# Qwiic_Mux.net
KiCad netlist of a schematic drawn in EAGLE
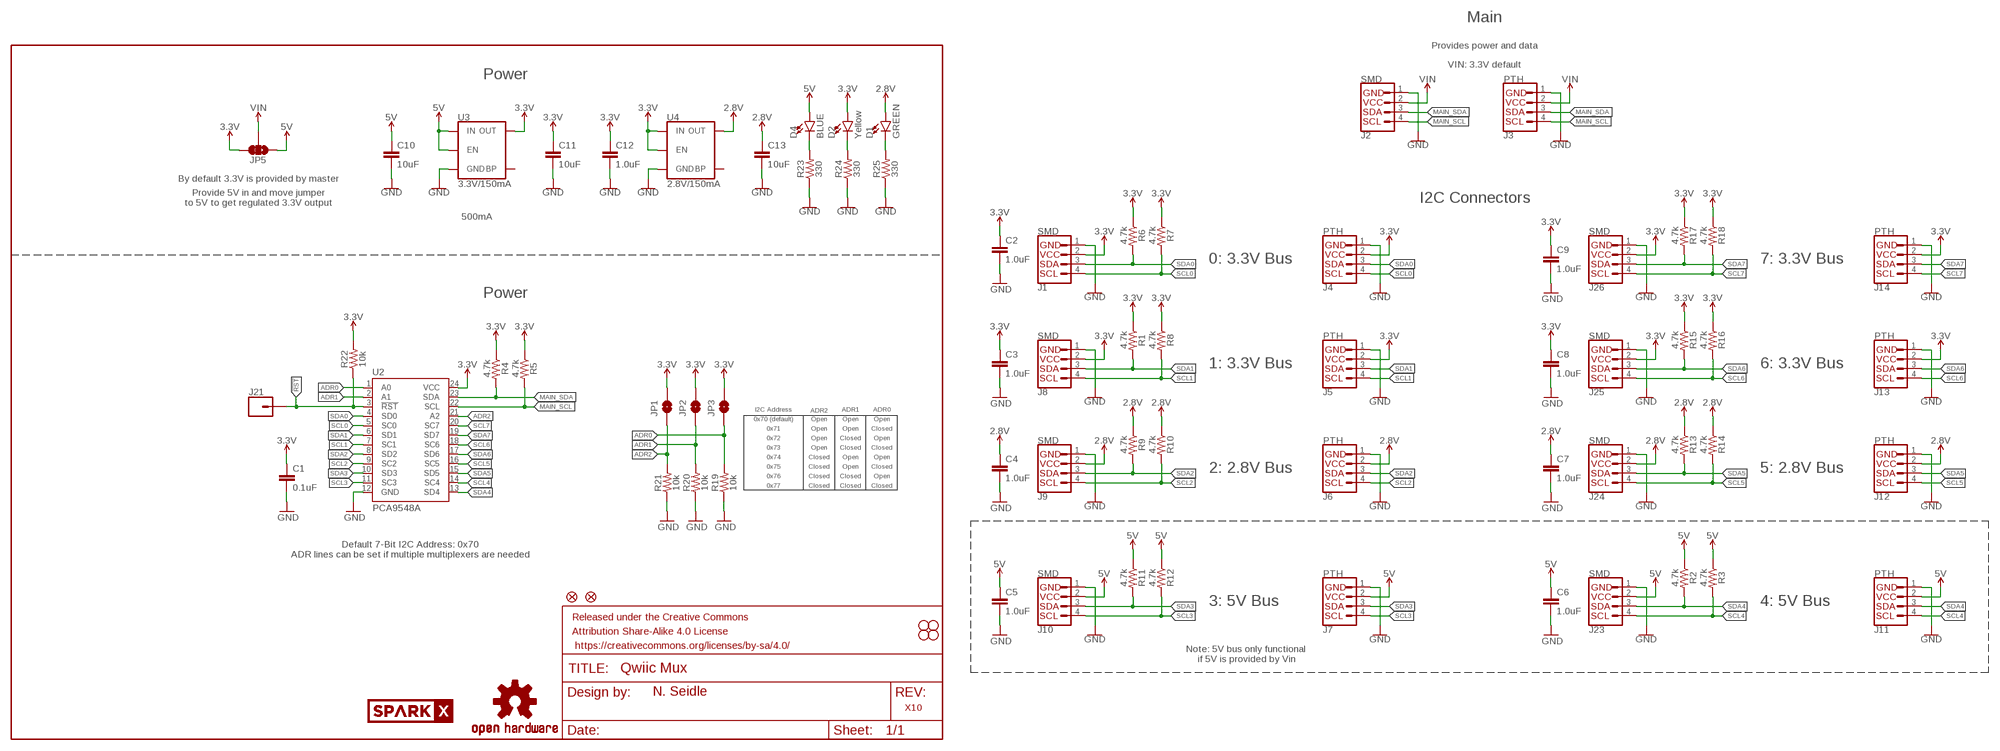
[diagram p0: schematic, sheet 1]

(export (version "E")
  (design (tool "Eeschema 10.0.6"))
  (components
    (comp (ref "C1")
      (value "0.1uF")
      (footprint "eagle-import:0603")
      (libsource (lib "eagle-import") (part "0.1UF-0603-25V-(+80/-20%)"))
    )
    (comp (ref "C2")
      (value "1.0uF")
      (footprint "eagle-import:0603")
      (libsource (lib "eagle-import") (part "1.0UF-0603-16V-10%"))
    )
    (comp (ref "C3")
      (value "1.0uF")
      (footprint "eagle-import:0603")
      (libsource (lib "eagle-import") (part "1.0UF-0603-16V-10%"))
    )
    (comp (ref "C4")
      (value "1.0uF")
      (footprint "eagle-import:0603")
      (libsource (lib "eagle-import") (part "1.0UF-0603-16V-10%"))
    )
    (comp (ref "C5")
      (value "1.0uF")
      (footprint "eagle-import:0603")
      (libsource (lib "eagle-import") (part "1.0UF-0603-16V-10%"))
    )
    (comp (ref "C6")
      (value "1.0uF")
      (footprint "eagle-import:0603")
      (libsource (lib "eagle-import") (part "1.0UF-0603-16V-10%"))
    )
    (comp (ref "C7")
      (value "1.0uF")
      (footprint "eagle-import:0603")
      (libsource (lib "eagle-import") (part "1.0UF-0603-16V-10%"))
    )
    (comp (ref "C8")
      (value "1.0uF")
      (footprint "eagle-import:0603")
      (libsource (lib "eagle-import") (part "1.0UF-0603-16V-10%"))
    )
    (comp (ref "C9")
      (value "1.0uF")
      (footprint "eagle-import:0603")
      (libsource (lib "eagle-import") (part "1.0UF-0603-16V-10%"))
    )
    (comp (ref "C10")
      (value "10uF")
      (footprint "eagle-import:0603")
      (libsource (lib "eagle-import") (part "10UF-0603-6.3V-20%"))
    )
    (comp (ref "C11")
      (value "10uF")
      (footprint "eagle-import:0603")
      (libsource (lib "eagle-import") (part "10UF-0603-6.3V-20%"))
    )
    (comp (ref "C12")
      (value "1.0uF")
      (footprint "eagle-import:0603")
      (libsource (lib "eagle-import") (part "1.0UF-0603-16V-10%"))
    )
    (comp (ref "C13")
      (value "10uF")
      (footprint "eagle-import:0603")
      (libsource (lib "eagle-import") (part "10UF-0603-6.3V-20%"))
    )
    (comp (ref "D1")
      (value "GREEN")
      (footprint "eagle-import:LED-0603")
      (libsource (lib "eagle-import") (part "LED-GREEN0603"))
    )
    (comp (ref "D2")
      (value "Yellow")
      (footprint "eagle-import:LED-0603")
      (libsource (lib "eagle-import") (part "LED-YELLOW0603"))
    )
    (comp (ref "D4")
      (value "BLUE")
      (footprint "eagle-import:LED-0603")
      (libsource (lib "eagle-import") (part "LED-BLUE0603"))
    )
    (comp (ref "FD1")
      (value "FIDUCIAL1X2")
      (footprint "eagle-import:FIDUCIAL-1X2")
      (libsource (lib "eagle-import") (part "FIDUCIAL1X2"))
    )
    (comp (ref "FD2")
      (value "FIDUCIAL1X2")
      (footprint "eagle-import:FIDUCIAL-1X2")
      (libsource (lib "eagle-import") (part "FIDUCIAL1X2"))
    )
    (comp (ref "FRAME1")
      (value "FRAME-LETTER")
      (footprint "eagle-import:CREATIVE_COMMONS")
      (libsource (lib "eagle-import") (part "FRAME-LETTER"))
    )
    (comp (ref "H1")
      (value "STAND-OFF")
      (footprint "eagle-import:STAND-OFF")
      (libsource (lib "eagle-import") (part "STAND-OFF"))
    )
    (comp (ref "H2")
      (value "STAND-OFF")
      (footprint "eagle-import:STAND-OFF")
      (libsource (lib "eagle-import") (part "STAND-OFF"))
    )
    (comp (ref "H3")
      (value "STAND-OFF")
      (footprint "eagle-import:STAND-OFF")
      (libsource (lib "eagle-import") (part "STAND-OFF"))
    )
    (comp (ref "H4")
      (value "STAND-OFF")
      (footprint "eagle-import:STAND-OFF")
      (libsource (lib "eagle-import") (part "STAND-OFF"))
    )
    (comp (ref "J1")
      (value "SMD")
      (footprint "eagle-import:1X04_1MM_RA")
      (libsource (lib "eagle-import") (part "I2C_STANDARDJS-1MM"))
    )
    (comp (ref "J2")
      (value "SMD")
      (footprint "eagle-import:1X04_1MM_RA")
      (libsource (lib "eagle-import") (part "I2C_STANDARDJS-1MM"))
    )
    (comp (ref "J3")
      (value "PTH")
      (footprint "eagle-import:1X04_NO_SILK")
      (libsource (lib "eagle-import") (part "I2C_STANDARD_NO_SILK"))
    )
    (comp (ref "J4")
      (value "PTH")
      (footprint "eagle-import:1X04_NO_SILK")
      (libsource (lib "eagle-import") (part "I2C_STANDARD_NO_SILK"))
    )
    (comp (ref "J5")
      (value "PTH")
      (footprint "eagle-import:1X04_NO_SILK")
      (libsource (lib "eagle-import") (part "I2C_STANDARD_NO_SILK"))
    )
    (comp (ref "J6")
      (value "PTH")
      (footprint "eagle-import:1X04_NO_SILK")
      (libsource (lib "eagle-import") (part "I2C_STANDARD_NO_SILK"))
    )
    (comp (ref "J7")
      (value "PTH")
      (footprint "eagle-import:1X04_NO_SILK")
      (libsource (lib "eagle-import") (part "I2C_STANDARD_NO_SILK"))
    )
    (comp (ref "J8")
      (value "SMD")
      (footprint "eagle-import:1X04_1MM_RA")
      (libsource (lib "eagle-import") (part "I2C_STANDARDJS-1MM"))
    )
    (comp (ref "J9")
      (value "SMD")
      (footprint "eagle-import:1X04_1MM_RA")
      (libsource (lib "eagle-import") (part "I2C_STANDARDJS-1MM"))
    )
    (comp (ref "J10")
      (value "SMD")
      (footprint "eagle-import:1X04_1MM_RA")
      (libsource (lib "eagle-import") (part "I2C_STANDARDJS-1MM"))
    )
    (comp (ref "J11")
      (value "PTH")
      (footprint "eagle-import:1X04_NO_SILK")
      (libsource (lib "eagle-import") (part "I2C_STANDARD_NO_SILK"))
    )
    (comp (ref "J12")
      (value "PTH")
      (footprint "eagle-import:1X04_NO_SILK")
      (libsource (lib "eagle-import") (part "I2C_STANDARD_NO_SILK"))
    )
    (comp (ref "J13")
      (value "PTH")
      (footprint "eagle-import:1X04_NO_SILK")
      (libsource (lib "eagle-import") (part "I2C_STANDARD_NO_SILK"))
    )
    (comp (ref "J14")
      (value "PTH")
      (footprint "eagle-import:1X04_NO_SILK")
      (libsource (lib "eagle-import") (part "I2C_STANDARD_NO_SILK"))
    )
    (comp (ref "J21")
      (value "CONN_01PTH_NO_SILK_YES_STOP")
      (footprint "eagle-import:1X01_NO_SILK")
      (libsource (lib "eagle-import") (part "CONN_01PTH_NO_SILK_YES_STOP"))
    )
    (comp (ref "J23")
      (value "SMD")
      (footprint "eagle-import:1X04_1MM_RA")
      (libsource (lib "eagle-import") (part "I2C_STANDARDJS-1MM"))
    )
    (comp (ref "J24")
      (value "SMD")
      (footprint "eagle-import:1X04_1MM_RA")
      (libsource (lib "eagle-import") (part "I2C_STANDARDJS-1MM"))
    )
    (comp (ref "J25")
      (value "SMD")
      (footprint "eagle-import:1X04_1MM_RA")
      (libsource (lib "eagle-import") (part "I2C_STANDARDJS-1MM"))
    )
    (comp (ref "J26")
      (value "SMD")
      (footprint "eagle-import:1X04_1MM_RA")
      (libsource (lib "eagle-import") (part "I2C_STANDARDJS-1MM"))
    )
    (comp (ref "JP1")
      (value "JUMPER-SMT_2_NO_SILK")
      (footprint "eagle-import:SMT-JUMPER_2_NO_SILK")
      (libsource (lib "eagle-import") (part "JUMPER-SMT_2_NO_SILK"))
    )
    (comp (ref "JP2")
      (value "JUMPER-SMT_2_NO_SILK")
      (footprint "eagle-import:SMT-JUMPER_2_NO_SILK")
      (libsource (lib "eagle-import") (part "JUMPER-SMT_2_NO_SILK"))
    )
    (comp (ref "JP3")
      (value "JUMPER-SMT_2_NO_SILK")
      (footprint "eagle-import:SMT-JUMPER_2_NO_SILK")
      (libsource (lib "eagle-import") (part "JUMPER-SMT_2_NO_SILK"))
    )
    (comp (ref "JP5")
      (value "JUMPER-SMT_3_1-NC_TRACE_SILK")
      (footprint "eagle-import:SMT-JUMPER_3_1-NC_TRACE_SILK")
      (libsource (lib "eagle-import") (part "JUMPER-SMT_3_1-NC_TRACE_SILK"))
    )
    (comp (ref "LOGO1")
      (value "OSHW-LOGOMINI")
      (footprint "eagle-import:OSHW-LOGO-MINI")
      (libsource (lib "eagle-import") (part "OSHW-LOGOMINI"))
    )
    (comp (ref "R1")
      (value "4.7k")
      (footprint "eagle-import:0603")
      (libsource (lib "eagle-import") (part "4.7KOHM-0603-1/10W-1%"))
    )
    (comp (ref "R2")
      (value "4.7k")
      (footprint "eagle-import:0603")
      (libsource (lib "eagle-import") (part "4.7KOHM-0603-1/10W-1%"))
    )
    (comp (ref "R3")
      (value "4.7k")
      (footprint "eagle-import:0603")
      (libsource (lib "eagle-import") (part "4.7KOHM-0603-1/10W-1%"))
    )
    (comp (ref "R4")
      (value "4.7k")
      (footprint "eagle-import:0603")
      (libsource (lib "eagle-import") (part "4.7KOHM-0603-1/10W-1%"))
    )
    (comp (ref "R5")
      (value "4.7k")
      (footprint "eagle-import:0603")
      (libsource (lib "eagle-import") (part "4.7KOHM-0603-1/10W-1%"))
    )
    (comp (ref "R6")
      (value "4.7k")
      (footprint "eagle-import:0603")
      (libsource (lib "eagle-import") (part "4.7KOHM-0603-1/10W-1%"))
    )
    (comp (ref "R7")
      (value "4.7k")
      (footprint "eagle-import:0603")
      (libsource (lib "eagle-import") (part "4.7KOHM-0603-1/10W-1%"))
    )
    (comp (ref "R8")
      (value "4.7k")
      (footprint "eagle-import:0603")
      (libsource (lib "eagle-import") (part "4.7KOHM-0603-1/10W-1%"))
    )
    (comp (ref "R9")
      (value "4.7k")
      (footprint "eagle-import:0603")
      (libsource (lib "eagle-import") (part "4.7KOHM-0603-1/10W-1%"))
    )
    (comp (ref "R10")
      (value "4.7k")
      (footprint "eagle-import:0603")
      (libsource (lib "eagle-import") (part "4.7KOHM-0603-1/10W-1%"))
    )
    (comp (ref "R11")
      (value "4.7k")
      (footprint "eagle-import:0603")
      (libsource (lib "eagle-import") (part "4.7KOHM-0603-1/10W-1%"))
    )
    (comp (ref "R12")
      (value "4.7k")
      (footprint "eagle-import:0603")
      (libsource (lib "eagle-import") (part "4.7KOHM-0603-1/10W-1%"))
    )
    (comp (ref "R13")
      (value "4.7k")
      (footprint "eagle-import:0603")
      (libsource (lib "eagle-import") (part "4.7KOHM-0603-1/10W-1%"))
    )
    (comp (ref "R14")
      (value "4.7k")
      (footprint "eagle-import:0603")
      (libsource (lib "eagle-import") (part "4.7KOHM-0603-1/10W-1%"))
    )
    (comp (ref "R15")
      (value "4.7k")
      (footprint "eagle-import:0603")
      (libsource (lib "eagle-import") (part "4.7KOHM-0603-1/10W-1%"))
    )
    (comp (ref "R16")
      (value "4.7k")
      (footprint "eagle-import:0603")
      (libsource (lib "eagle-import") (part "4.7KOHM-0603-1/10W-1%"))
    )
    (comp (ref "R17")
      (value "4.7k")
      (footprint "eagle-import:0603")
      (libsource (lib "eagle-import") (part "4.7KOHM-0603-1/10W-1%"))
    )
    (comp (ref "R18")
      (value "4.7k")
      (footprint "eagle-import:0603")
      (libsource (lib "eagle-import") (part "4.7KOHM-0603-1/10W-1%"))
    )
    (comp (ref "R19")
      (value "10k")
      (footprint "eagle-import:0603")
      (libsource (lib "eagle-import") (part "10KOHM-0603-1/10W-1%"))
    )
    (comp (ref "R20")
      (value "10k")
      (footprint "eagle-import:0603")
      (libsource (lib "eagle-import") (part "10KOHM-0603-1/10W-1%"))
    )
    (comp (ref "R21")
      (value "10k")
      (footprint "eagle-import:0603")
      (libsource (lib "eagle-import") (part "10KOHM-0603-1/10W-1%"))
    )
    (comp (ref "R22")
      (value "10k")
      (footprint "eagle-import:0603")
      (libsource (lib "eagle-import") (part "10KOHM-0603-1/10W-1%"))
    )
    (comp (ref "R23")
      (value "330")
      (footprint "eagle-import:0603")
      (libsource (lib "eagle-import") (part "330OHM-0603-1/10W-1%"))
    )
    (comp (ref "R24")
      (value "330")
      (footprint "eagle-import:0603")
      (libsource (lib "eagle-import") (part "330OHM-0603-1/10W-1%"))
    )
    (comp (ref "R25")
      (value "330")
      (footprint "eagle-import:0603")
      (libsource (lib "eagle-import") (part "330OHM-0603-1/10W-1%"))
    )
    (comp (ref "U$1")
      (value "SPARKX-LOGO3")
      (footprint "eagle-import:SPARKX-SMALL")
      (libsource (lib "eagle-import") (part "SPARKX-LOGO3"))
    )
    (comp (ref "U$2")
      (value "SPARKX-LOGO5")
      (footprint "eagle-import:SPARKX-LARGE")
      (libsource (lib "eagle-import") (part "SPARKX-LOGO5"))
    )
    (comp (ref "U2")
      (value "PCA9548A")
      (footprint "eagle-import:TSSOP28")
      (libsource (lib "eagle-import") (part "TCA9548A"))
    )
    (comp (ref "U3")
      (value "3.3V/150mA")
      (footprint "eagle-import:SOT23-5")
      (libsource (lib "eagle-import") (part "V_REG_MIC52053.3V"))
    )
    (comp (ref "U4")
      (value "2.8V/150mA")
      (footprint "eagle-import:SOT23-5")
      (libsource (lib "eagle-import") (part "V_REG_MIC52053.3V"))
    )
  )
  (nets
    (net (code "1") (name "/~{RST}") (class "Default")
      (node (ref "J21") (pin "1") (pinfunction "1_1") (pintype "passive"))
      (node (ref "R22") (pin "1") (pinfunction "1_1") (pintype "passive"))
      (node (ref "U2") (pin "3") (pinfunction "~{RST}_3") (pintype "bidirectional"))
    )
    (net (code "2") (name "2.8V") (class "Default")
      (node (ref "C13") (pin "1") (pinfunction "1_1") (pintype "passive"))
      (node (ref "C4") (pin "1") (pinfunction "1_1") (pintype "passive"))
      (node (ref "C7") (pin "1") (pinfunction "1_1") (pintype "passive"))
      (node (ref "D1") (pin "A") (pinfunction "A_A") (pintype "passive"))
      (node (ref "J12") (pin "2") (pinfunction "VCC_2") (pintype "power_in"))
      (node (ref "J24") (pin "2") (pinfunction "VCC_2") (pintype "power_in"))
      (node (ref "J6") (pin "2") (pinfunction "VCC_2") (pintype "power_in"))
      (node (ref "J9") (pin "2") (pinfunction "VCC_2") (pintype "power_in"))
      (node (ref "R10") (pin "1") (pinfunction "1_1") (pintype "passive"))
      (node (ref "R13") (pin "1") (pinfunction "1_1") (pintype "passive"))
      (node (ref "R14") (pin "1") (pinfunction "1_1") (pintype "passive"))
      (node (ref "R9") (pin "1") (pinfunction "1_1") (pintype "passive"))
      (node (ref "U4") (pin "5") (pinfunction "OUT_5") (pintype "passive"))
    )
    (net (code "3") (name "3.3V") (class "Default")
      (node (ref "C1") (pin "1") (pinfunction "1_1") (pintype "passive"))
      (node (ref "C11") (pin "1") (pinfunction "1_1") (pintype "passive"))
      (node (ref "C12") (pin "1") (pinfunction "1_1") (pintype "passive"))
      (node (ref "C2") (pin "1") (pinfunction "1_1") (pintype "passive"))
      (node (ref "C3") (pin "1") (pinfunction "1_1") (pintype "passive"))
      (node (ref "C8") (pin "1") (pinfunction "1_1") (pintype "passive"))
      (node (ref "C9") (pin "1") (pinfunction "1_1") (pintype "passive"))
      (node (ref "D2") (pin "A") (pinfunction "A_A") (pintype "passive"))
      (node (ref "J1") (pin "2") (pinfunction "VCC_2") (pintype "power_in"))
      (node (ref "J13") (pin "2") (pinfunction "VCC_2") (pintype "power_in"))
      (node (ref "J14") (pin "2") (pinfunction "VCC_2") (pintype "power_in"))
      (node (ref "J25") (pin "2") (pinfunction "VCC_2") (pintype "power_in"))
      (node (ref "J26") (pin "2") (pinfunction "VCC_2") (pintype "power_in"))
      (node (ref "J4") (pin "2") (pinfunction "VCC_2") (pintype "power_in"))
      (node (ref "J5") (pin "2") (pinfunction "VCC_2") (pintype "power_in"))
      (node (ref "J8") (pin "2") (pinfunction "VCC_2") (pintype "power_in"))
      (node (ref "JP1") (pin "2") (pinfunction "2_2") (pintype "passive"))
      (node (ref "JP2") (pin "2") (pinfunction "2_2") (pintype "passive"))
      (node (ref "JP3") (pin "2") (pinfunction "2_2") (pintype "passive"))
      (node (ref "JP5") (pin "3") (pinfunction "3_3") (pintype "passive"))
      (node (ref "R1") (pin "1") (pinfunction "1_1") (pintype "passive"))
      (node (ref "R15") (pin "1") (pinfunction "1_1") (pintype "passive"))
      (node (ref "R16") (pin "1") (pinfunction "1_1") (pintype "passive"))
      (node (ref "R17") (pin "1") (pinfunction "1_1") (pintype "passive"))
      (node (ref "R18") (pin "1") (pinfunction "1_1") (pintype "passive"))
      (node (ref "R22") (pin "2") (pinfunction "2_2") (pintype "passive"))
      (node (ref "R4") (pin "1") (pinfunction "1_1") (pintype "passive"))
      (node (ref "R5") (pin "1") (pinfunction "1_1") (pintype "passive"))
      (node (ref "R6") (pin "1") (pinfunction "1_1") (pintype "passive"))
      (node (ref "R7") (pin "1") (pinfunction "1_1") (pintype "passive"))
      (node (ref "R8") (pin "1") (pinfunction "1_1") (pintype "passive"))
      (node (ref "U2") (pin "24") (pinfunction "VCC_24") (pintype "bidirectional"))
      (node (ref "U3") (pin "5") (pinfunction "OUT_5") (pintype "passive"))
      (node (ref "U4") (pin "1") (pinfunction "IN_1") (pintype "input"))
      (node (ref "U4") (pin "3") (pinfunction "EN_3") (pintype "input"))
    )
    (net (code "4") (name "5V") (class "Default")
      (node (ref "C10") (pin "1") (pinfunction "1_1") (pintype "passive"))
      (node (ref "C5") (pin "1") (pinfunction "1_1") (pintype "passive"))
      (node (ref "C6") (pin "1") (pinfunction "1_1") (pintype "passive"))
      (node (ref "D4") (pin "A") (pinfunction "A_A") (pintype "passive"))
      (node (ref "J10") (pin "2") (pinfunction "VCC_2") (pintype "power_in"))
      (node (ref "J11") (pin "2") (pinfunction "VCC_2") (pintype "power_in"))
      (node (ref "J23") (pin "2") (pinfunction "VCC_2") (pintype "power_in"))
      (node (ref "J7") (pin "2") (pinfunction "VCC_2") (pintype "power_in"))
      (node (ref "JP5") (pin "1") (pinfunction "1_1") (pintype "passive"))
      (node (ref "R11") (pin "1") (pinfunction "1_1") (pintype "passive"))
      (node (ref "R12") (pin "1") (pinfunction "1_1") (pintype "passive"))
      (node (ref "R2") (pin "1") (pinfunction "1_1") (pintype "passive"))
      (node (ref "R3") (pin "1") (pinfunction "1_1") (pintype "passive"))
      (node (ref "U3") (pin "1") (pinfunction "IN_1") (pintype "input"))
      (node (ref "U3") (pin "3") (pinfunction "EN_3") (pintype "input"))
    )
    (net (code "5") (name "ADR0") (class "Default")
      (node (ref "JP3") (pin "1") (pinfunction "1_1") (pintype "passive"))
      (node (ref "R19") (pin "2") (pinfunction "2_2") (pintype "passive"))
      (node (ref "U2") (pin "1") (pinfunction "A0_1") (pintype "bidirectional"))
    )
    (net (code "6") (name "ADR1") (class "Default")
      (node (ref "JP2") (pin "1") (pinfunction "1_1") (pintype "passive"))
      (node (ref "R20") (pin "2") (pinfunction "2_2") (pintype "passive"))
      (node (ref "U2") (pin "2") (pinfunction "A1_2") (pintype "bidirectional"))
    )
    (net (code "7") (name "ADR2") (class "Default")
      (node (ref "JP1") (pin "1") (pinfunction "1_1") (pintype "passive"))
      (node (ref "R21") (pin "2") (pinfunction "2_2") (pintype "passive"))
      (node (ref "U2") (pin "21") (pinfunction "A2_21") (pintype "bidirectional"))
    )
    (net (code "8") (name "GND") (class "Default")
      (node (ref "C1") (pin "2") (pinfunction "2_2") (pintype "passive"))
      (node (ref "C10") (pin "2") (pinfunction "2_2") (pintype "passive"))
      (node (ref "C11") (pin "2") (pinfunction "2_2") (pintype "passive"))
      (node (ref "C12") (pin "2") (pinfunction "2_2") (pintype "passive"))
      (node (ref "C13") (pin "2") (pinfunction "2_2") (pintype "passive"))
      (node (ref "C2") (pin "2") (pinfunction "2_2") (pintype "passive"))
      (node (ref "C3") (pin "2") (pinfunction "2_2") (pintype "passive"))
      (node (ref "C4") (pin "2") (pinfunction "2_2") (pintype "passive"))
      (node (ref "C5") (pin "2") (pinfunction "2_2") (pintype "passive"))
      (node (ref "C6") (pin "2") (pinfunction "2_2") (pintype "passive"))
      (node (ref "C7") (pin "2") (pinfunction "2_2") (pintype "passive"))
      (node (ref "C8") (pin "2") (pinfunction "2_2") (pintype "passive"))
      (node (ref "C9") (pin "2") (pinfunction "2_2") (pintype "passive"))
      (node (ref "J1") (pin "1") (pinfunction "GND_1") (pintype "power_in"))
      (node (ref "J10") (pin "1") (pinfunction "GND_1") (pintype "power_in"))
      (node (ref "J11") (pin "1") (pinfunction "GND_1") (pintype "power_in"))
      (node (ref "J12") (pin "1") (pinfunction "GND_1") (pintype "power_in"))
      (node (ref "J13") (pin "1") (pinfunction "GND_1") (pintype "power_in"))
      (node (ref "J14") (pin "1") (pinfunction "GND_1") (pintype "power_in"))
      (node (ref "J2") (pin "1") (pinfunction "GND_1") (pintype "power_in"))
      (node (ref "J23") (pin "1") (pinfunction "GND_1") (pintype "power_in"))
      (node (ref "J24") (pin "1") (pinfunction "GND_1") (pintype "power_in"))
      (node (ref "J25") (pin "1") (pinfunction "GND_1") (pintype "power_in"))
      (node (ref "J26") (pin "1") (pinfunction "GND_1") (pintype "power_in"))
      (node (ref "J3") (pin "1") (pinfunction "GND_1") (pintype "power_in"))
      (node (ref "J4") (pin "1") (pinfunction "GND_1") (pintype "power_in"))
      (node (ref "J5") (pin "1") (pinfunction "GND_1") (pintype "power_in"))
      (node (ref "J6") (pin "1") (pinfunction "GND_1") (pintype "power_in"))
      (node (ref "J7") (pin "1") (pinfunction "GND_1") (pintype "power_in"))
      (node (ref "J8") (pin "1") (pinfunction "GND_1") (pintype "power_in"))
      (node (ref "J9") (pin "1") (pinfunction "GND_1") (pintype "power_in"))
      (node (ref "R19") (pin "1") (pinfunction "1_1") (pintype "passive"))
      (node (ref "R20") (pin "1") (pinfunction "1_1") (pintype "passive"))
      (node (ref "R21") (pin "1") (pinfunction "1_1") (pintype "passive"))
      (node (ref "R23") (pin "1") (pinfunction "1_1") (pintype "passive"))
      (node (ref "R24") (pin "1") (pinfunction "1_1") (pintype "passive"))
      (node (ref "R25") (pin "1") (pinfunction "1_1") (pintype "passive"))
      (node (ref "U2") (pin "12") (pinfunction "GND_12") (pintype "bidirectional"))
      (node (ref "U3") (pin "2") (pinfunction "GND_2") (pintype "input"))
      (node (ref "U4") (pin "2") (pinfunction "GND_2") (pintype "input"))
    )
    (net (code "9") (name "MAIN_SCL") (class "Default")
      (node (ref "J2") (pin "4") (pinfunction "SCL_4") (pintype "passive"))
      (node (ref "J3") (pin "4") (pinfunction "SCL_4") (pintype "passive"))
      (node (ref "R5") (pin "2") (pinfunction "2_2") (pintype "passive"))
      (node (ref "U2") (pin "22") (pinfunction "SCL_22") (pintype "bidirectional"))
    )
    (net (code "10") (name "MAIN_SDA") (class "Default")
      (node (ref "J2") (pin "3") (pinfunction "SDA_3") (pintype "passive"))
      (node (ref "J3") (pin "3") (pinfunction "SDA_3") (pintype "passive"))
      (node (ref "R4") (pin "2") (pinfunction "2_2") (pintype "passive"))
      (node (ref "U2") (pin "23") (pinfunction "SDA_23") (pintype "bidirectional"))
    )
    (net (code "11") (name "Net-(D1-PadC)") (class "Default")
      (node (ref "D1") (pin "C") (pinfunction "C_C") (pintype "passive"))
      (node (ref "R25") (pin "2") (pinfunction "2_2") (pintype "passive"))
    )
    (net (code "12") (name "Net-(D2-PadC)") (class "Default")
      (node (ref "D2") (pin "C") (pinfunction "C_C") (pintype "passive"))
      (node (ref "R24") (pin "2") (pinfunction "2_2") (pintype "passive"))
    )
    (net (code "13") (name "Net-(D4-PadC)") (class "Default")
      (node (ref "D4") (pin "C") (pinfunction "C_C") (pintype "passive"))
      (node (ref "R23") (pin "2") (pinfunction "2_2") (pintype "passive"))
    )
    (net (code "14") (name "SCL0") (class "Default")
      (node (ref "J1") (pin "4") (pinfunction "SCL_4") (pintype "passive"))
      (node (ref "J4") (pin "4") (pinfunction "SCL_4") (pintype "passive"))
      (node (ref "R7") (pin "2") (pinfunction "2_2") (pintype "passive"))
      (node (ref "U2") (pin "5") (pinfunction "SC0_5") (pintype "bidirectional"))
    )
    (net (code "15") (name "SCL1") (class "Default")
      (node (ref "J5") (pin "4") (pinfunction "SCL_4") (pintype "passive"))
      (node (ref "J8") (pin "4") (pinfunction "SCL_4") (pintype "passive"))
      (node (ref "R8") (pin "2") (pinfunction "2_2") (pintype "passive"))
      (node (ref "U2") (pin "7") (pinfunction "SC1_7") (pintype "bidirectional"))
    )
    (net (code "16") (name "SCL2") (class "Default")
      (node (ref "J6") (pin "4") (pinfunction "SCL_4") (pintype "passive"))
      (node (ref "J9") (pin "4") (pinfunction "SCL_4") (pintype "passive"))
      (node (ref "R10") (pin "2") (pinfunction "2_2") (pintype "passive"))
      (node (ref "U2") (pin "9") (pinfunction "SC2_9") (pintype "bidirectional"))
    )
    (net (code "17") (name "SCL3") (class "Default")
      (node (ref "J10") (pin "4") (pinfunction "SCL_4") (pintype "passive"))
      (node (ref "J7") (pin "4") (pinfunction "SCL_4") (pintype "passive"))
      (node (ref "R12") (pin "2") (pinfunction "2_2") (pintype "passive"))
      (node (ref "U2") (pin "11") (pinfunction "SC3_11") (pintype "bidirectional"))
    )
    (net (code "18") (name "SCL4") (class "Default")
      (node (ref "J11") (pin "4") (pinfunction "SCL_4") (pintype "passive"))
      (node (ref "J23") (pin "4") (pinfunction "SCL_4") (pintype "passive"))
      (node (ref "R3") (pin "2") (pinfunction "2_2") (pintype "passive"))
      (node (ref "U2") (pin "14") (pinfunction "SC4_14") (pintype "bidirectional"))
    )
    (net (code "19") (name "SCL5") (class "Default")
      (node (ref "J12") (pin "4") (pinfunction "SCL_4") (pintype "passive"))
      (node (ref "J24") (pin "4") (pinfunction "SCL_4") (pintype "passive"))
      (node (ref "R14") (pin "2") (pinfunction "2_2") (pintype "passive"))
      (node (ref "U2") (pin "16") (pinfunction "SC5_16") (pintype "bidirectional"))
    )
    (net (code "20") (name "SCL6") (class "Default")
      (node (ref "J13") (pin "4") (pinfunction "SCL_4") (pintype "passive"))
      (node (ref "J25") (pin "4") (pinfunction "SCL_4") (pintype "passive"))
      (node (ref "R16") (pin "2") (pinfunction "2_2") (pintype "passive"))
      (node (ref "U2") (pin "18") (pinfunction "SC6_18") (pintype "bidirectional"))
    )
    (net (code "21") (name "SCL7") (class "Default")
      (node (ref "J14") (pin "4") (pinfunction "SCL_4") (pintype "passive"))
      (node (ref "J26") (pin "4") (pinfunction "SCL_4") (pintype "passive"))
      (node (ref "R18") (pin "2") (pinfunction "2_2") (pintype "passive"))
      (node (ref "U2") (pin "20") (pinfunction "SC7_20") (pintype "bidirectional"))
    )
    (net (code "22") (name "SDA0") (class "Default")
      (node (ref "J1") (pin "3") (pinfunction "SDA_3") (pintype "passive"))
      (node (ref "J4") (pin "3") (pinfunction "SDA_3") (pintype "passive"))
      (node (ref "R6") (pin "2") (pinfunction "2_2") (pintype "passive"))
      (node (ref "U2") (pin "4") (pinfunction "SD0_4") (pintype "bidirectional"))
    )
    (net (code "23") (name "SDA1") (class "Default")
      (node (ref "J5") (pin "3") (pinfunction "SDA_3") (pintype "passive"))
      (node (ref "J8") (pin "3") (pinfunction "SDA_3") (pintype "passive"))
      (node (ref "R1") (pin "2") (pinfunction "2_2") (pintype "passive"))
      (node (ref "U2") (pin "6") (pinfunction "SD1_6") (pintype "bidirectional"))
    )
    (net (code "24") (name "SDA2") (class "Default")
      (node (ref "J6") (pin "3") (pinfunction "SDA_3") (pintype "passive"))
      (node (ref "J9") (pin "3") (pinfunction "SDA_3") (pintype "passive"))
      (node (ref "R9") (pin "2") (pinfunction "2_2") (pintype "passive"))
      (node (ref "U2") (pin "8") (pinfunction "SD2_8") (pintype "bidirectional"))
    )
    (net (code "25") (name "SDA3") (class "Default")
      (node (ref "J10") (pin "3") (pinfunction "SDA_3") (pintype "passive"))
      (node (ref "J7") (pin "3") (pinfunction "SDA_3") (pintype "passive"))
      (node (ref "R11") (pin "2") (pinfunction "2_2") (pintype "passive"))
      (node (ref "U2") (pin "10") (pinfunction "SD3_10") (pintype "bidirectional"))
    )
    (net (code "26") (name "SDA4") (class "Default")
      (node (ref "J11") (pin "3") (pinfunction "SDA_3") (pintype "passive"))
      (node (ref "J23") (pin "3") (pinfunction "SDA_3") (pintype "passive"))
      (node (ref "R2") (pin "2") (pinfunction "2_2") (pintype "passive"))
      (node (ref "U2") (pin "13") (pinfunction "SD4_13") (pintype "bidirectional"))
    )
    (net (code "27") (name "SDA5") (class "Default")
      (node (ref "J12") (pin "3") (pinfunction "SDA_3") (pintype "passive"))
      (node (ref "J24") (pin "3") (pinfunction "SDA_3") (pintype "passive"))
      (node (ref "R13") (pin "2") (pinfunction "2_2") (pintype "passive"))
      (node (ref "U2") (pin "15") (pinfunction "SD5_15") (pintype "bidirectional"))
    )
    (net (code "28") (name "SDA6") (class "Default")
      (node (ref "J13") (pin "3") (pinfunction "SDA_3") (pintype "passive"))
      (node (ref "J25") (pin "3") (pinfunction "SDA_3") (pintype "passive"))
      (node (ref "R15") (pin "2") (pinfunction "2_2") (pintype "passive"))
      (node (ref "U2") (pin "17") (pinfunction "SD6_17") (pintype "bidirectional"))
    )
    (net (code "29") (name "SDA7") (class "Default")
      (node (ref "J14") (pin "3") (pinfunction "SDA_3") (pintype "passive"))
      (node (ref "J26") (pin "3") (pinfunction "SDA_3") (pintype "passive"))
      (node (ref "R17") (pin "2") (pinfunction "2_2") (pintype "passive"))
      (node (ref "U2") (pin "19") (pinfunction "SD7_19") (pintype "bidirectional"))
    )
    (net (code "30") (name "VIN") (class "Default")
      (node (ref "J2") (pin "2") (pinfunction "VCC_2") (pintype "power_in"))
      (node (ref "J3") (pin "2") (pinfunction "VCC_2") (pintype "power_in"))
      (node (ref "JP5") (pin "2") (pinfunction "2_2") (pintype "passive"))
    )
    (net (code "31") (name "unconnected-(U3-BP-Pad4)") (class "Default")
      (node (ref "U3") (pin "4") (pinfunction "BP_4") (pintype "input"))
    )
    (net (code "32") (name "unconnected-(U4-BP-Pad4)") (class "Default")
      (node (ref "U4") (pin "4") (pinfunction "BP_4") (pintype "input"))
    )
  )
)
